# CCU-2-ICs.net
KiCad netlist of a schematic drawn in Altium Designer
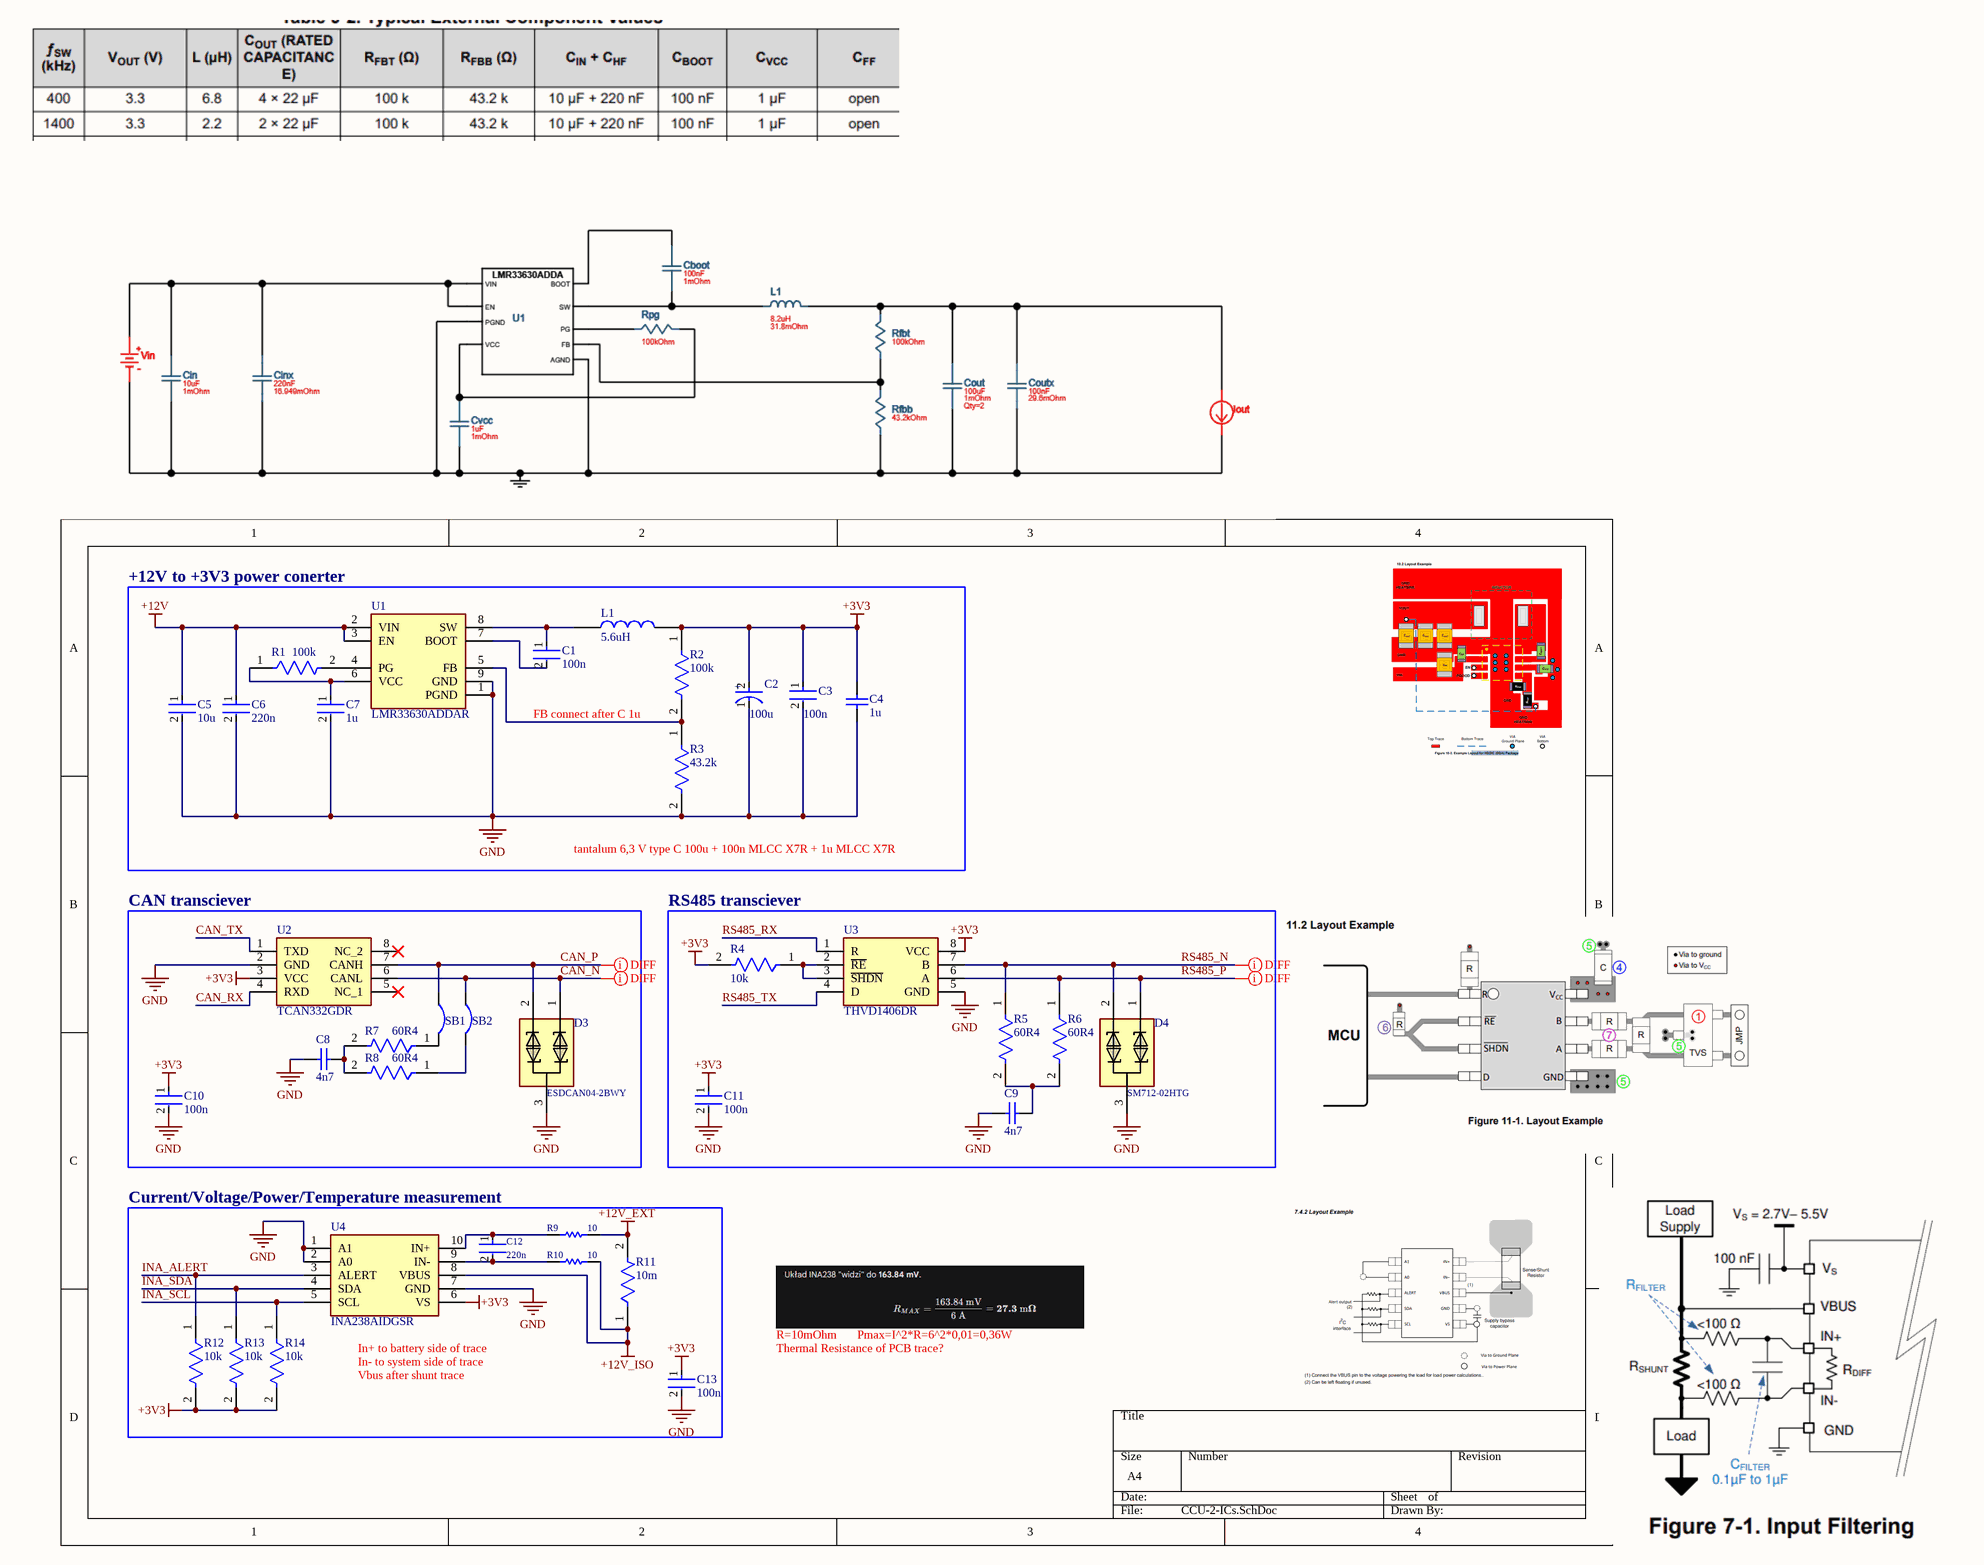
[diagram p0: CCU-2-ICs.SchDoc]

(export (version "E")
  (design (tool "Eeschema 10.0.6"))
  (components
    (comp (ref "C1")
      (value "100n")
      (footprint "FP-C0603C-CF-MFG")
      (description "CAP CER 0.1UF 25V X7R 0603")
      (fields
        (field (name "MANUFACTURER PART NUMBER") "C0603C104K3RACTU")
        (field (name "OCTOPART") "https://octopart.com/c0603c104k3ractu-kemet-127541")
      )
      (libsource (lib "Altium Content Vault") (part "b4654b650e69147ec39a6b967a45e02"))
    )
    (comp (ref "C2")
      (value "100u")
      (footprint "FP-TPSC-MFG")
      (description "CAP TANT 100UF 10% 10V 2312")
      (fields (field (name "VOLTAGE") "10V") (field (name "TOLERANCE") "10%"))
      (libsource (lib "Altium Content Vault") (part "cf48714ba7e38822c1575c7ec0b6d1f"))
    )
    (comp (ref "C3")
      (value "100n")
      (footprint "FP-C0603C-CF-MFG")
      (description "CAP CER 0.1UF 25V X7R 0603")
      (fields
        (field (name "MANUFACTURER PART NUMBER") "C0603C104K3RACTU")
        (field (name "OCTOPART") "https://octopart.com/c0603c104k3ractu-kemet-127541")
      )
      (libsource (lib "Altium Content Vault") (part "b4654b650e69147ec39a6b967a45e02"))
    )
    (comp (ref "C4")
      (value "1u")
      (footprint "CAPC2013X140X50ML20T25")
      (fields
        (field (name "MANUFACTURER") "AVX Interconnect / Elco")
        (field (name "PART NUMBER") "0805ZC105JAT2A")
      )
      (libsource (lib "Altium Content Vault") (part "CAP"))
    )
    (comp (ref "C5")
      (value "10u")
      (footprint "FP-CL32-IPC_C")
      (description "Cap Ceramic 10uF 50V X7R ±10% SMD 1210 +125°C Embossed T/R")
      (fields (field (name "TOLERANCE") "10%") (field (name "VOLTAGE") "50V"))
      (libsource (lib "Altium Content Vault") (part "b4654b650e69147ec39a6b967a45e02"))
    )
    (comp (ref "C6")
      (value "220n")
      (footprint "FP-C2012-125-0_2-IPC_C")
      (description "Multilayer Ceramic Capacitors 220nF ±10% 50V X7R SMD 0805")
      (fields (field (name "VOLTAGE") "50V") (field (name "TOLERANCE") "10%"))
      (libsource (lib "Altium Content Vault") (part "b4654b650e69147ec39a6b967a45e02"))
    )
    (comp (ref "C7")
      (value "1u")
      (footprint "FP-CC0805-0_85-MFG")
      (description "CAP CER 1UF 25V X7R 0805")
      (fields (field (name "MANUFACTURER PART NUMBER") "CC0805KKX7R8BB105") (field (name "TOLERANCE") "0.1"))
      (libsource (lib "Altium Content Vault") (part "11868f565c42a9108669ba33697ecf6"))
    )
    (comp (ref "C8")
      (value "4n7")
      (footprint "CAPC2013X145X48NL20T23")
      (fields (field (name "MANUFACTURER") "Vitramon") (field (name "PART NUMBER") "VJ0805Y222JXAAC"))
      (libsource (lib "Altium Content Vault") (part "CAP"))
    )
    (comp (ref "C9")
      (value "4n7")
      (footprint "CAPC2013X145X48NL20T23")
      (fields (field (name "MANUFACTURER") "Vitramon") (field (name "PART NUMBER") "VJ0805Y222JXAAC"))
      (libsource (lib "Altium Content Vault") (part "CAP"))
    )
    (comp (ref "C10")
      (value "100n")
      (footprint "FP-C0603C-CF-MFG")
      (description "CAP CER 0.1UF 25V X7R 0603")
      (fields
        (field (name "MANUFACTURER PART NUMBER") "C0603C104K3RACTU")
        (field (name "OCTOPART") "https://octopart.com/c0603c104k3ractu-kemet-127541")
      )
      (libsource (lib "Altium Content Vault") (part "b4654b650e69147ec39a6b967a45e02"))
    )
    (comp (ref "C11")
      (value "100n")
      (footprint "FP-C0603C-CF-MFG")
      (description "CAP CER 0.1UF 25V X7R 0603")
      (fields
        (field (name "MANUFACTURER PART NUMBER") "C0603C104K3RACTU")
        (field (name "OCTOPART") "https://octopart.com/c0603c104k3ractu-kemet-127541")
      )
      (libsource (lib "Altium Content Vault") (part "b4654b650e69147ec39a6b967a45e02"))
    )
    (comp (ref "C12")
      (value "220n")
      (footprint "FP-C2012-125-0_2-IPC_C")
      (description "Multilayer Ceramic Capacitors 220nF ±10% 50V X7R SMD 0805")
      (fields (field (name "VOLTAGE") "50V") (field (name "TOLERANCE") "10%"))
      (libsource (lib "Altium Content Vault") (part "b4654b650e69147ec39a6b967a45e02"))
    )
    (comp (ref "C13")
      (value "100n")
      (footprint "FP-C0603C-CF-MFG")
      (description "CAP CER 0.1UF 25V X7R 0603")
      (fields
        (field (name "MANUFACTURER PART NUMBER") "C0603C104K3RACTU")
        (field (name "OCTOPART") "https://octopart.com/c0603c104k3ractu-kemet-127541")
      )
      (libsource (lib "Altium Content Vault") (part "b4654b650e69147ec39a6b967a45e02"))
    )
    (comp (ref "D3")
      (value "ESDCAN04-2BWY")
      (footprint "ESDCAN04-2BWY")
      (description "TVS DIODE 25.5VWM 43VC SOT323-3 / 43V Clamp 3.7A (8/20µs) Ipp Tvs Diode Surface Mount SOT-323-3")
      (fields (field (name "MANUFACTURER") "STMicroelectronics"))
      (libsource (lib "HydrogreenLibrary") (part "ESDCAN04-2BWY"))
    )
    (comp (ref "D4")
      (value "SM712-02HTG")
      (footprint "FP-SM712-MFG")
      (description "SM712 Series 31 V 600 W Surface Mount Asymmetrical TVS Diode Array - SOT-23-3")
      (fields (field (name "MANUFACTURER") "Littelfuse"))
      (libsource (lib "HydrogreenLibrary") (part "SM712-02HTG"))
    )
    (comp (ref "L1")
      (value "5.6uH")
      (footprint "XAL7070472MEC")
      (description "General Purpose Inductor, 4.7uH, 20%, 1 Element, Composite-Core, SMD, 3028")
      (fields
        (field (name "MOUSER PART NUMBER") "994-XAL7070-472MEC")
        (field (name "MANUFACTURER_PART_NUMBER") "XAL7070-472MEC")
      )
      (libsource (lib "HydrogreenLibrary") (part "XAL7070-472MEC"))
    )
    (comp (ref "R1")
      (value "100k")
      (footprint "FP-RC0603-0_55-MFG")
      (description "RES SMD 100K OHM 1% 1/10W 0603")
      (fields (field (name "TOLERANCE") "1%"))
      (libsource (lib "Altium Content Vault") (part "1029c3af85768c4190bb7ad29bc67b5"))
    )
    (comp (ref "R2")
      (value "100k")
      (footprint "FP-RC0603-0_55-MFG")
      (description "RES SMD 100K OHM 1% 1/10W 0603")
      (fields (field (name "TOLERANCE") "1%"))
      (libsource (lib "Altium Content Vault") (part "1029c3af85768c4190bb7ad29bc67b5"))
    )
    (comp (ref "R3")
      (value "43.2k")
      (footprint "FP-RC0603-0_55-MFG")
      (description "RES SMD 43.2K OHM 1% 1/10W 0603")
      (fields (field (name "TOLERANCE") "1%"))
      (libsource (lib "Altium Content Vault") (part "1029c3af85768c4190bb7ad29bc67b5"))
    )
    (comp (ref "R4")
      (value "10k")
      (footprint "FP-RC0603-0_55-IPC_C")
      (description "RES 10K OHM 1% 1/10W 0603")
      (fields (field (name "TOLERANCE") "1%"))
      (libsource (lib "Altium Content Vault") (part "1029c3af85768c4190bb7ad29bc67b5"))
    )
    (comp (ref "R5")
      (value "60R4")
      (footprint "FP-CRCW0603-e3-IPC_C")
      (description "RES Thick Film, 60.4Ω, 1%, 0.1W, 100ppm/°C, 0603")
      (fields (field (name "TOLERANCE") "1%"))
      (libsource (lib "Altium Content Vault") (part "1029c3af85768c4190bb7ad29bc67b5"))
    )
    (comp (ref "R6")
      (value "60R4")
      (footprint "FP-CRCW0603-e3-IPC_C")
      (description "RES Thick Film, 60.4Ω, 1%, 0.1W, 100ppm/°C, 0603")
      (fields (field (name "TOLERANCE") "1%"))
      (libsource (lib "Altium Content Vault") (part "1029c3af85768c4190bb7ad29bc67b5"))
    )
    (comp (ref "R7")
      (value "60R4")
      (footprint "FP-CRCW0603-e3-IPC_C")
      (description "RES Thick Film, 60.4Ω, 1%, 0.1W, 100ppm/°C, 0603")
      (fields (field (name "TOLERANCE") "1%"))
      (libsource (lib "Altium Content Vault") (part "1029c3af85768c4190bb7ad29bc67b5"))
    )
    (comp (ref "R8")
      (value "60R4")
      (footprint "FP-CRCW0603-e3-IPC_C")
      (description "RES Thick Film, 60.4Ω, 1%, 0.1W, 100ppm/°C, 0603")
      (fields (field (name "TOLERANCE") "1%"))
      (libsource (lib "Altium Content Vault") (part "1029c3af85768c4190bb7ad29bc67b5"))
    )
    (comp (ref "R9")
      (value "10")
      (footprint "RESC1608X55X25NL10T15")
      (description "Chip Resistor, 10 Ohm, +/- 1%, 0.1 W, -55 to 155 degC, 0603 (1608 Metric), RoHS, Tape and Reel")
      (fields (field (name "MANUFACTURER") "Yageo"))
      (libsource (lib "Altium Content Vault") (part "RES-2"))
    )
    (comp (ref "R10")
      (value "10")
      (footprint "RESC1608X55X25NL10T15")
      (description "Chip Resistor, 10 Ohm, +/- 1%, 0.1 W, -55 to 155 degC, 0603 (1608 Metric), RoHS, Tape and Reel")
      (fields (field (name "MANUFACTURER") "Yageo"))
      (libsource (lib "Altium Content Vault") (part "RES-2"))
    )
    (comp (ref "R11")
      (value "10m")
      (footprint "FP-CSRF2512-IPC_C")
      (description "Foil on Ceramic Current Sensing Chip Resistor 43mΩ ±1% 2W 2512 AEC Qualified")
      (fields (field (name "TOLERANCE") "1%"))
      (libsource (lib "Altium Content Vault") (part "1029c3af85768c4190bb7ad29bc67b5"))
    )
    (comp (ref "R12")
      (value "10k")
      (footprint "FP-RC0603-0_55-IPC_C")
      (description "RES 10K OHM 1% 1/10W 0603")
      (fields (field (name "TOLERANCE") "1%"))
      (libsource (lib "Altium Content Vault") (part "1029c3af85768c4190bb7ad29bc67b5"))
    )
    (comp (ref "R13")
      (value "10k")
      (footprint "FP-RC0603-0_55-IPC_C")
      (description "RES 10K OHM 1% 1/10W 0603")
      (fields (field (name "TOLERANCE") "1%"))
      (libsource (lib "Altium Content Vault") (part "1029c3af85768c4190bb7ad29bc67b5"))
    )
    (comp (ref "R14")
      (value "10k")
      (footprint "FP-RC0603-0_55-IPC_C")
      (description "RES 10K OHM 1% 1/10W 0603")
      (fields (field (name "TOLERANCE") "1%"))
      (libsource (lib "Altium Content Vault") (part "1029c3af85768c4190bb7ad29bc67b5"))
    )
    (comp (ref "SB1")
      (value "Solder_Bridge")
      (footprint "Solder Bridge")
      (description "Bridge 0.5mm gap, 2mm width")
      (libsource (lib "HydrogreenLibrary") (part "Solder_Bridge"))
    )
    (comp (ref "SB2")
      (value "Solder_Bridge")
      (footprint "Solder Bridge")
      (description "Bridge 0.5mm gap, 2mm width")
      (libsource (lib "HydrogreenLibrary") (part "Solder_Bridge"))
    )
    (comp (ref "U1")
      (value "LMR33630ADDAR")
      (footprint "LMR33630ADDAR")
      (fields
        (field (name "MOUSER PART NUMBER") "595-LMR33630ADDAR")
        (field (name "MANUFACTURER") "Texas Instruments")
      )
      (libsource (lib "HydrogreenLibrary") (part "LMR33630ADDAR"))
    )
    (comp (ref "U2")
      (value "TCAN332GDR")
      (footprint "SOIC127P600X175-8N")
      (description "3.3-V CAN Transceivers with CAN FD (Flexible Data Rate) 8-SOIC -40 to 125")
      (fields (field (name "MANUFACTURER") "Texas Instruments"))
      (libsource (lib "HydrogreenLibrary") (part "TCAN332GDR"))
    )
    (comp (ref "U3")
      (value "THVD1406DR")
      (footprint "SOIC127P600X175-8N")
      (fields (field (name "MANUFACTURER") "Texas Instruments"))
      (libsource (lib "HydrogreenLibrary") (part "THVD1406DR"))
    )
    (comp (ref "U4")
      (value "INA238AIDGSR")
      (footprint "INA238AIDGSR")
      (fields
        (field (name "MOUSER PART NUMBER") "595-INA238AIDGSR")
        (field (name "MANUFACTURER") "Texas Instruments")
      )
      (libsource (lib "HydrogreenLibrary") (part "INA238AIDGSR"))
    )
  )
  (nets
    (net (code "1") (name "+3V3") (class "Default")
      (node (ref "C10") (pin "1") (pinfunction "1_1") (pintype "passive"))
      (node (ref "C11") (pin "1") (pinfunction "1_1") (pintype "passive"))
      (node (ref "C13") (pin "1") (pinfunction "1_1") (pintype "passive"))
      (node (ref "C2") (pin "2") (pinfunction "A_2") (pintype "passive"))
      (node (ref "C3") (pin "1") (pinfunction "1_1") (pintype "passive"))
      (node (ref "C4") (pin "2") (pinfunction "2_2") (pintype "passive"))
      (node (ref "L1") (pin "2") (pinfunction "2_2") (pintype "passive"))
      (node (ref "R12") (pin "2") (pinfunction "2_2") (pintype "passive"))
      (node (ref "R13") (pin "2") (pinfunction "2_2") (pintype "passive"))
      (node (ref "R14") (pin "2") (pinfunction "2_2") (pintype "passive"))
      (node (ref "R2") (pin "1") (pinfunction "1_1") (pintype "passive"))
      (node (ref "R4") (pin "2") (pinfunction "2_2") (pintype "passive"))
      (node (ref "U2") (pin "3") (pinfunction "VCC_3") (pintype "passive"))
      (node (ref "U3") (pin "8") (pinfunction "VCC_8") (pintype "passive"))
      (node (ref "U4") (pin "6") (pinfunction "VS_6") (pintype "passive"))
    )
    (net (code "2") (name "+12V") (class "Default")
      (node (ref "C5") (pin "1") (pinfunction "1_1") (pintype "passive"))
      (node (ref "C6") (pin "1") (pinfunction "1_1") (pintype "passive"))
      (node (ref "U1") (pin "2") (pinfunction "VIN_2") (pintype "passive"))
      (node (ref "U1") (pin "3") (pinfunction "EN_3") (pintype "passive"))
    )
    (net (code "3") (name "+12V_EXT") (class "Default")
      (node (ref "R11") (pin "2") (pinfunction "2_2") (pintype "passive"))
      (node (ref "R9") (pin "2") (pinfunction "2_2") (pintype "passive"))
    )
    (net (code "4") (name "+12V_ISO") (class "Default")
      (node (ref "R10") (pin "2") (pinfunction "2_2") (pintype "passive"))
      (node (ref "R11") (pin "1") (pinfunction "1_1") (pintype "passive"))
      (node (ref "U4") (pin "8") (pinfunction "VBUS_8") (pintype "passive"))
    )
    (net (code "5") (name "/CAN_N") (class "Default")
      (node (ref "D3") (pin "1") (pintype "passive"))
      (node (ref "SB2") (pin "1") (pinfunction "1_1") (pintype "passive"))
      (node (ref "U2") (pin "6") (pinfunction "CANL_6") (pintype "passive"))
    )
    (net (code "6") (name "/CAN_P") (class "Default")
      (node (ref "D3") (pin "2") (pintype "passive"))
      (node (ref "SB1") (pin "1") (pinfunction "1_1") (pintype "passive"))
      (node (ref "U2") (pin "7") (pinfunction "CANH_7") (pintype "passive"))
    )
    (net (code "7") (name "/CAN_RX") (class "Default")
      (node (ref "U2") (pin "4") (pinfunction "RXD_4") (pintype "passive"))
    )
    (net (code "8") (name "/CAN_TX") (class "Default")
      (node (ref "U2") (pin "1") (pinfunction "TXD_1") (pintype "passive"))
    )
    (net (code "9") (name "/INA_ALERT") (class "Default")
      (node (ref "R12") (pin "1") (pinfunction "1_1") (pintype "passive"))
      (node (ref "U4") (pin "3") (pinfunction "ALERT_3") (pintype "passive"))
    )
    (net (code "10") (name "/INA_SCL") (class "Default")
      (node (ref "R14") (pin "1") (pinfunction "1_1") (pintype "passive"))
      (node (ref "U4") (pin "5") (pinfunction "SCL_5") (pintype "passive"))
    )
    (net (code "11") (name "/INA_SDA") (class "Default")
      (node (ref "R13") (pin "1") (pinfunction "1_1") (pintype "passive"))
      (node (ref "U4") (pin "4") (pinfunction "SDA_4") (pintype "passive"))
    )
    (net (code "12") (name "/RS485_N") (class "Default")
      (node (ref "D4") (pin "2") (pintype "passive"))
      (node (ref "R5") (pin "1") (pinfunction "1_1") (pintype "passive"))
      (node (ref "U3") (pin "7") (pinfunction "B_7") (pintype "passive"))
    )
    (net (code "13") (name "/RS485_P") (class "Default")
      (node (ref "D4") (pin "1") (pintype "passive"))
      (node (ref "R6") (pin "1") (pinfunction "1_1") (pintype "passive"))
      (node (ref "U3") (pin "6") (pinfunction "A_6") (pintype "passive"))
    )
    (net (code "14") (name "/RS485_RX") (class "Default")
      (node (ref "U3") (pin "1") (pinfunction "R_1") (pintype "passive"))
    )
    (net (code "15") (name "/RS485_TX") (class "Default")
      (node (ref "U3") (pin "4") (pinfunction "D_4") (pintype "passive"))
    )
    (net (code "16") (name "GND") (class "Default")
      (node (ref "C10") (pin "2") (pinfunction "2_2") (pintype "passive"))
      (node (ref "C11") (pin "2") (pinfunction "2_2") (pintype "passive"))
      (node (ref "C13") (pin "2") (pinfunction "2_2") (pintype "passive"))
      (node (ref "C2") (pin "1") (pinfunction "C_1") (pintype "passive"))
      (node (ref "C3") (pin "2") (pinfunction "2_2") (pintype "passive"))
      (node (ref "C4") (pin "1") (pinfunction "1_1") (pintype "passive"))
      (node (ref "C5") (pin "2") (pinfunction "2_2") (pintype "passive"))
      (node (ref "C6") (pin "2") (pinfunction "2_2") (pintype "passive"))
      (node (ref "C7") (pin "2") (pinfunction "2_2") (pintype "passive"))
      (node (ref "C8") (pin "1") (pinfunction "1_1") (pintype "passive"))
      (node (ref "C9") (pin "1") (pinfunction "1_1") (pintype "passive"))
      (node (ref "D3") (pin "3") (pintype "passive"))
      (node (ref "D4") (pin "3") (pintype "passive"))
      (node (ref "R3") (pin "2") (pinfunction "2_2") (pintype "passive"))
      (node (ref "U1") (pin "1") (pinfunction "PGND_1") (pintype "passive"))
      (node (ref "U1") (pin "9") (pinfunction "GND_9") (pintype "passive"))
      (node (ref "U2") (pin "2") (pinfunction "GND_2") (pintype "passive"))
      (node (ref "U3") (pin "5") (pinfunction "GND_5") (pintype "passive"))
      (node (ref "U4") (pin "1") (pinfunction "A1_1") (pintype "passive"))
      (node (ref "U4") (pin "2") (pinfunction "A0_2") (pintype "passive"))
      (node (ref "U4") (pin "7") (pinfunction "GND_7") (pintype "passive"))
    )
    (net (code "17") (name "Net-(C8-Pad2)") (class "Default")
      (node (ref "C8") (pin "2") (pinfunction "2_2") (pintype "passive"))
      (node (ref "R7") (pin "2") (pinfunction "2_2") (pintype "passive"))
      (node (ref "R8") (pin "2") (pinfunction "2_2") (pintype "passive"))
    )
    (net (code "18") (name "Net-(C9-Pad2)") (class "Default")
      (node (ref "C9") (pin "2") (pinfunction "2_2") (pintype "passive"))
      (node (ref "R5") (pin "2") (pinfunction "2_2") (pintype "passive"))
      (node (ref "R6") (pin "2") (pinfunction "2_2") (pintype "passive"))
    )
    (net (code "19") (name "Net-(R7-Pad1)") (class "Default")
      (node (ref "R7") (pin "1") (pinfunction "1_1") (pintype "passive"))
      (node (ref "SB1") (pin "2") (pinfunction "2_2") (pintype "passive"))
    )
    (net (code "20") (name "Net-(R8-Pad1)") (class "Default")
      (node (ref "R8") (pin "1") (pinfunction "1_1") (pintype "passive"))
      (node (ref "SB2") (pin "2") (pinfunction "2_2") (pintype "passive"))
    )
    (net (code "21") (name "Net-(U1-BOOT)") (class "Default")
      (node (ref "C1") (pin "2") (pinfunction "2_2") (pintype "passive"))
      (node (ref "U1") (pin "7") (pinfunction "BOOT_7") (pintype "passive"))
    )
    (net (code "22") (name "Net-(U1-FB)") (class "Default")
      (node (ref "R2") (pin "2") (pinfunction "2_2") (pintype "passive"))
      (node (ref "R3") (pin "1") (pinfunction "1_1") (pintype "passive"))
      (node (ref "U1") (pin "5") (pinfunction "FB_5") (pintype "passive"))
    )
    (net (code "23") (name "Net-(U1-PG)") (class "Default")
      (node (ref "R1") (pin "2") (pinfunction "2_2") (pintype "passive"))
      (node (ref "U1") (pin "4") (pinfunction "PG_4") (pintype "passive"))
    )
    (net (code "24") (name "Net-(U1-SW)") (class "Default")
      (node (ref "C1") (pin "1") (pinfunction "1_1") (pintype "passive"))
      (node (ref "L1") (pin "1") (pinfunction "1_1") (pintype "passive"))
      (node (ref "U1") (pin "8") (pinfunction "SW_8") (pintype "passive"))
    )
    (net (code "25") (name "Net-(U1-VCC)") (class "Default")
      (node (ref "C7") (pin "1") (pinfunction "1_1") (pintype "passive"))
      (node (ref "R1") (pin "1") (pinfunction "1_1") (pintype "passive"))
      (node (ref "U1") (pin "6") (pinfunction "VCC_6") (pintype "passive"))
    )
    (net (code "26") (name "Net-(U3-~{RE})") (class "Default")
      (node (ref "R4") (pin "1") (pinfunction "1_1") (pintype "passive"))
      (node (ref "U3") (pin "2") (pinfunction "~{RE}_2") (pintype "passive"))
      (node (ref "U3") (pin "3") (pinfunction "~{SHDN}_3") (pintype "passive"))
    )
    (net (code "27") (name "Net-(U4-IN+)") (class "Default")
      (node (ref "C12") (pin "1") (pinfunction "1_1") (pintype "passive"))
      (node (ref "R9") (pin "1") (pinfunction "1_1") (pintype "passive"))
      (node (ref "U4") (pin "10") (pinfunction "IN+_10") (pintype "passive"))
    )
    (net (code "28") (name "Net-(U4-IN-)") (class "Default")
      (node (ref "C12") (pin "2") (pinfunction "2_2") (pintype "passive"))
      (node (ref "R10") (pin "1") (pinfunction "1_1") (pintype "passive"))
      (node (ref "U4") (pin "9") (pinfunction "IN-_9") (pintype "passive"))
    )
    (net (code "29") (name "unconnected-(U2-NC_1-Pad5)") (class "Default")
      (node (ref "U2") (pin "5") (pinfunction "NC_1_5") (pintype "passive+no_connect"))
    )
    (net (code "30") (name "unconnected-(U2-NC_2-Pad8)") (class "Default")
      (node (ref "U2") (pin "8") (pinfunction "NC_2_8") (pintype "passive+no_connect"))
    )
  )
)
